# STM32_FYP_ADC_Module.net
KiCad netlist of a schematic drawn in Altium Designer
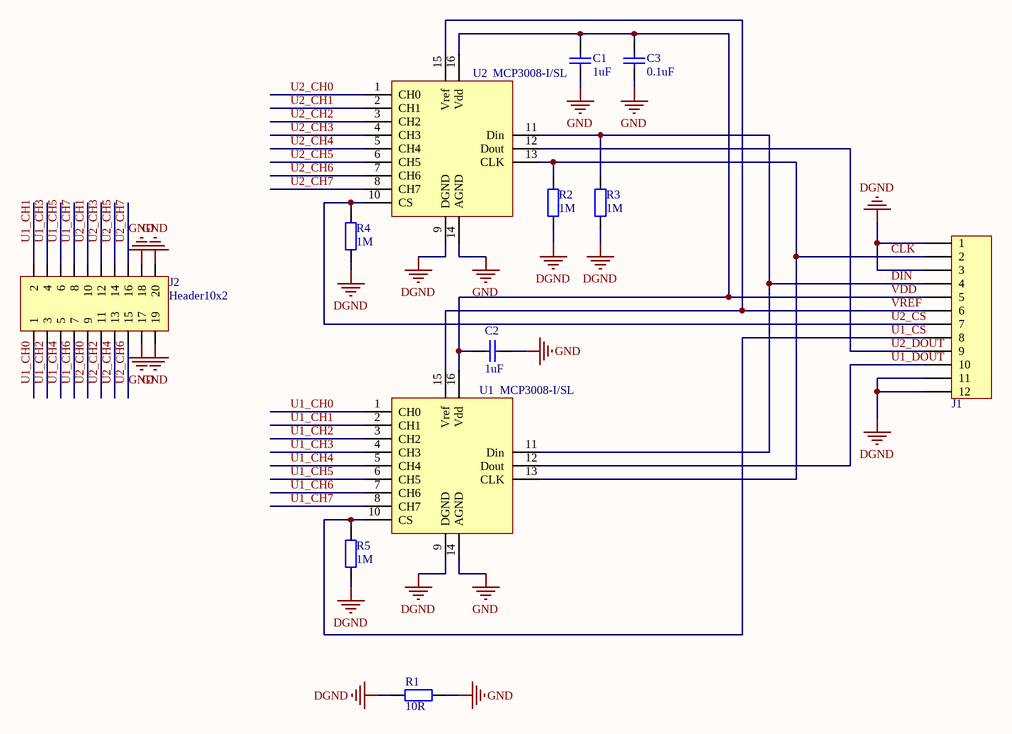
[diagram p0: STM32_FYP_ADC_Module.SchDoc]

(export (version "E")
  (design (tool "Eeschema 10.0.6"))
  (components
    (comp (ref "C1")
      (value "1uF")
      (footprint "0805C_M")
      (description "无极性电容")
      (fields (field (name "PUBLISHER") "Altium Limited"))
      (libsource (lib "USER") (part "Cap"))
    )
    (comp (ref "C2")
      (value "1uF")
      (footprint "0805C_M")
      (description "无极性电容")
      (fields (field (name "PUBLISHER") "Altium Limited"))
      (libsource (lib "USER") (part "Cap"))
    )
    (comp (ref "C3")
      (value "0.1uF")
      (footprint "0805C_M")
      (description "无极性电容")
      (fields (field (name "PUBLISHER") "Altium Limited"))
      (libsource (lib "USER") (part "Cap"))
    )
    (comp (ref "J1")
      (value "Header12")
      (footprint "USER:12P-2.54-H")
      (description "12PIN插座")
      (libsource (lib "USER") (part "Header12"))
    )
    (comp (ref "J2")
      (value "Header10x2")
      (footprint "USER:10PX2-2.54 - H")
      (libsource (lib "USER") (part "Header10x2"))
    )
    (comp (ref "R1")
      (value "10R")
      (footprint "0805R_M")
      (description "电阻")
      (fields (field (name "PUBLISHER") "Altium Limited"))
      (libsource (lib "USER") (part "Res"))
    )
    (comp (ref "R2")
      (value "1M")
      (footprint "0805R_M")
      (description "电阻")
      (fields (field (name "PUBLISHER") "Altium Limited"))
      (libsource (lib "") (part "Res_1"))
    )
    (comp (ref "R3")
      (value "1M")
      (footprint "0805R_M")
      (description "电阻")
      (fields (field (name "PUBLISHER") "Altium Limited"))
      (libsource (lib "") (part "Res_1"))
    )
    (comp (ref "R4")
      (value "1M")
      (footprint "0805R_M")
      (description "电阻")
      (fields (field (name "PUBLISHER") "Altium Limited"))
      (libsource (lib "") (part "Res_1"))
    )
    (comp (ref "R5")
      (value "1M")
      (footprint "0805R_M")
      (description "电阻")
      (fields (field (name "PUBLISHER") "Altium Limited"))
      (libsource (lib "") (part "Res_1"))
    )
    (comp (ref "U1")
      (value "MCP3008-I/SL")
      (footprint "user1:SOIC-16_150mil")
      (description "ADC模数转换芯片")
      (libsource (lib "GUEST") (part "MCP3008"))
    )
    (comp (ref "U2")
      (value "MCP3008-I/SL")
      (footprint "user1:SOIC-16_150mil")
      (description "ADC模数转换芯片")
      (libsource (lib "GUEST") (part "MCP3008"))
    )
  )
  (nets
    (net (code "1") (name "/CLK") (class "Default")
      (node (ref "J1") (pin "2") (pinfunction "2_2") (pintype "passive"))
      (node (ref "R2") (pin "1") (pinfunction "1_1") (pintype "passive"))
      (node (ref "U1") (pin "13") (pinfunction "CLK_13") (pintype "passive"))
      (node (ref "U2") (pin "13") (pinfunction "CLK_13") (pintype "passive"))
    )
    (net (code "2") (name "/DIN") (class "Default")
      (node (ref "J1") (pin "4") (pinfunction "4_4") (pintype "passive"))
      (node (ref "R3") (pin "1") (pinfunction "1_1") (pintype "passive"))
      (node (ref "U1") (pin "11") (pinfunction "Din_11") (pintype "passive"))
      (node (ref "U2") (pin "11") (pinfunction "Din_11") (pintype "passive"))
    )
    (net (code "3") (name "/U1_CH0") (class "Default")
      (node (ref "J2") (pin "1") (pinfunction "1_1") (pintype "passive"))
      (node (ref "U1") (pin "1") (pinfunction "CH0_1") (pintype "passive"))
    )
    (net (code "4") (name "/U1_CH1") (class "Default")
      (node (ref "J2") (pin "2") (pinfunction "2_2") (pintype "passive"))
      (node (ref "U1") (pin "2") (pinfunction "CH1_2") (pintype "passive"))
    )
    (net (code "5") (name "/U1_CH2") (class "Default")
      (node (ref "J2") (pin "3") (pinfunction "3_3") (pintype "passive"))
      (node (ref "U1") (pin "3") (pinfunction "CH2_3") (pintype "passive"))
    )
    (net (code "6") (name "/U1_CH3") (class "Default")
      (node (ref "J2") (pin "4") (pinfunction "4_4") (pintype "passive"))
      (node (ref "U1") (pin "4") (pinfunction "CH3_4") (pintype "passive"))
    )
    (net (code "7") (name "/U1_CH4") (class "Default")
      (node (ref "J2") (pin "5") (pinfunction "5_5") (pintype "passive"))
      (node (ref "U1") (pin "5") (pinfunction "CH4_5") (pintype "passive"))
    )
    (net (code "8") (name "/U1_CH5") (class "Default")
      (node (ref "J2") (pin "6") (pinfunction "6_6") (pintype "passive"))
      (node (ref "U1") (pin "6") (pinfunction "CH5_6") (pintype "passive"))
    )
    (net (code "9") (name "/U1_CH6") (class "Default")
      (node (ref "J2") (pin "7") (pinfunction "7_7") (pintype "passive"))
      (node (ref "U1") (pin "7") (pinfunction "CH6_7") (pintype "passive"))
    )
    (net (code "10") (name "/U1_CH7") (class "Default")
      (node (ref "J2") (pin "8") (pinfunction "8_8") (pintype "passive"))
      (node (ref "U1") (pin "8") (pinfunction "CH7_8") (pintype "passive"))
    )
    (net (code "11") (name "/U1_CS") (class "Default")
      (node (ref "J1") (pin "8") (pinfunction "8_8") (pintype "passive"))
      (node (ref "R5") (pin "1") (pinfunction "1_1") (pintype "passive"))
      (node (ref "U1") (pin "10") (pinfunction "CS_10") (pintype "passive"))
    )
    (net (code "12") (name "/U1_DOUT") (class "Default")
      (node (ref "J1") (pin "10") (pinfunction "10_10") (pintype "passive"))
      (node (ref "U1") (pin "12") (pinfunction "Dout_12") (pintype "passive"))
    )
    (net (code "13") (name "/U2_CH0") (class "Default")
      (node (ref "J2") (pin "9") (pinfunction "9_9") (pintype "passive"))
      (node (ref "U2") (pin "1") (pinfunction "CH0_1") (pintype "passive"))
    )
    (net (code "14") (name "/U2_CH1") (class "Default")
      (node (ref "J2") (pin "10") (pinfunction "10_10") (pintype "passive"))
      (node (ref "U2") (pin "2") (pinfunction "CH1_2") (pintype "passive"))
    )
    (net (code "15") (name "/U2_CH2") (class "Default")
      (node (ref "J2") (pin "11") (pinfunction "11_11") (pintype "passive"))
      (node (ref "U2") (pin "3") (pinfunction "CH2_3") (pintype "passive"))
    )
    (net (code "16") (name "/U2_CH3") (class "Default")
      (node (ref "J2") (pin "12") (pinfunction "12_12") (pintype "passive"))
      (node (ref "U2") (pin "4") (pinfunction "CH3_4") (pintype "passive"))
    )
    (net (code "17") (name "/U2_CH4") (class "Default")
      (node (ref "J2") (pin "13") (pinfunction "13_13") (pintype "passive"))
      (node (ref "U2") (pin "5") (pinfunction "CH4_5") (pintype "passive"))
    )
    (net (code "18") (name "/U2_CH5") (class "Default")
      (node (ref "J2") (pin "14") (pinfunction "14_14") (pintype "passive"))
      (node (ref "U2") (pin "6") (pinfunction "CH5_6") (pintype "passive"))
    )
    (net (code "19") (name "/U2_CH6") (class "Default")
      (node (ref "J2") (pin "15") (pinfunction "15_15") (pintype "passive"))
      (node (ref "U2") (pin "7") (pinfunction "CH6_7") (pintype "passive"))
    )
    (net (code "20") (name "/U2_CH7") (class "Default")
      (node (ref "J2") (pin "16") (pinfunction "16_16") (pintype "passive"))
      (node (ref "U2") (pin "8") (pinfunction "CH7_8") (pintype "passive"))
    )
    (net (code "21") (name "/U2_CS") (class "Default")
      (node (ref "J1") (pin "7") (pinfunction "7_7") (pintype "passive"))
      (node (ref "R4") (pin "1") (pinfunction "1_1") (pintype "passive"))
      (node (ref "U2") (pin "10") (pinfunction "CS_10") (pintype "passive"))
    )
    (net (code "22") (name "/U2_DOUT") (class "Default")
      (node (ref "J1") (pin "9") (pinfunction "9_9") (pintype "passive"))
      (node (ref "U2") (pin "12") (pinfunction "Dout_12") (pintype "passive"))
    )
    (net (code "23") (name "/VDD") (class "Default")
      (node (ref "C1") (pin "2") (pinfunction "2_2") (pintype "passive"))
      (node (ref "C2") (pin "2") (pinfunction "2_2") (pintype "passive"))
      (node (ref "C3") (pin "1") (pinfunction "1_1") (pintype "passive"))
      (node (ref "J1") (pin "5") (pinfunction "5_5") (pintype "passive"))
      (node (ref "U1") (pin "16") (pinfunction "Vdd_16") (pintype "passive"))
      (node (ref "U2") (pin "16") (pinfunction "Vdd_16") (pintype "passive"))
    )
    (net (code "24") (name "/VREF") (class "Default")
      (node (ref "J1") (pin "6") (pinfunction "6_6") (pintype "passive"))
      (node (ref "U1") (pin "15") (pinfunction "Vref_15") (pintype "passive"))
      (node (ref "U2") (pin "15") (pinfunction "Vref_15") (pintype "passive"))
    )
    (net (code "25") (name "DGND") (class "Default")
      (node (ref "J1") (pin "1") (pinfunction "1_1") (pintype "passive"))
      (node (ref "J1") (pin "11") (pinfunction "11_11") (pintype "passive"))
      (node (ref "J1") (pin "12") (pinfunction "12_12") (pintype "passive"))
      (node (ref "J1") (pin "3") (pinfunction "3_3") (pintype "passive"))
      (node (ref "R1") (pin "1") (pinfunction "1_1") (pintype "passive"))
      (node (ref "R2") (pin "2") (pinfunction "2_2") (pintype "passive"))
      (node (ref "R3") (pin "2") (pinfunction "2_2") (pintype "passive"))
      (node (ref "R4") (pin "2") (pinfunction "2_2") (pintype "passive"))
      (node (ref "R5") (pin "2") (pinfunction "2_2") (pintype "passive"))
      (node (ref "U1") (pin "9") (pinfunction "DGND_9") (pintype "passive"))
      (node (ref "U2") (pin "9") (pinfunction "DGND_9") (pintype "passive"))
    )
    (net (code "26") (name "GND") (class "Default")
      (node (ref "C1") (pin "1") (pinfunction "1_1") (pintype "passive"))
      (node (ref "C2") (pin "1") (pinfunction "1_1") (pintype "passive"))
      (node (ref "C3") (pin "2") (pinfunction "2_2") (pintype "passive"))
      (node (ref "J2") (pin "17") (pinfunction "17_17") (pintype "passive"))
      (node (ref "J2") (pin "18") (pinfunction "18_18") (pintype "passive"))
      (node (ref "J2") (pin "19") (pinfunction "19_19") (pintype "passive"))
      (node (ref "J2") (pin "20") (pinfunction "20_20") (pintype "passive"))
      (node (ref "R1") (pin "2") (pinfunction "2_2") (pintype "passive"))
      (node (ref "U1") (pin "14") (pinfunction "AGND_14") (pintype "passive"))
      (node (ref "U2") (pin "14") (pinfunction "AGND_14") (pintype "passive"))
    )
  )
)
